# BSPD_Timing.net
KiCad netlist of a schematic drawn in Altium Designer
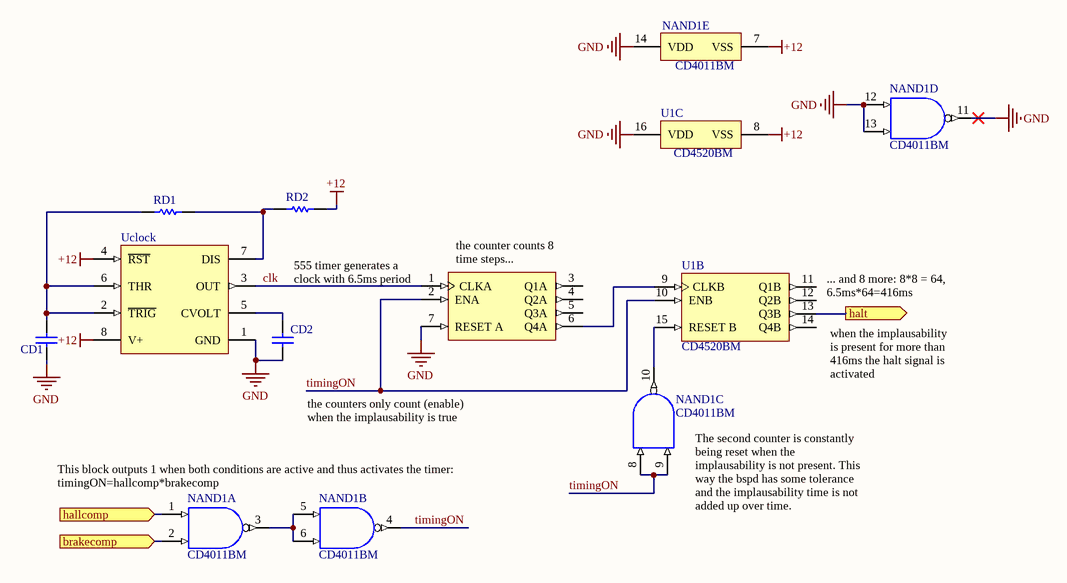
[diagram p0: BSPD_Timing.SchDoc]

(export (version "E")
  (design (tool "Eeschema 10.0.6"))
  (components
    (comp (ref "CD1")
      (value "CAP 68nF")
      (footprint "CAPC1206(3216)100_M")
      (description "CAP 68nF 50V -20% to +80% 1206 (3216 Metric) Thickness 1mm SMD")
      (fields (field (name "TOLERANCE") "-20% to +80%"))
      (libsource (lib "Altium Content Vault") (part "CAP"))
    )
    (comp (ref "CD2")
      (value "CAP 10nF")
      (footprint "CAPC1206(3216)110_M")
      (description "CAP 10nF 10V ±10% 1206 (3216 Metric) Thickness 1.05mm SMD")
      (fields (field (name "TOLERANCE") "Â±10%"))
      (libsource (lib "Altium Content Vault") (part "CAP"))
    )
    (comp (ref "NAND1")
      (value "CD4011BM")
      (footprint "D0014A_M")
      (description "CMOS Quad 2-Input NAND Gate, D0014A, TUBE")
      (fields
        (field (name "MANUFACTURER") "Texas Instruments")
        (field (name "GENERIC PART NUMBER") "CD4011B")
      )
      (libsource (lib "") (part "TI-NAND-4-2IN-14_A_1"))
    )
    (comp (ref "RD1")
      (value "68K")
      (footprint "RESC1206(3216)_M")
      (description "68K 0.25W 5% 1206 (3216 Metric)  SMD")
      (fields (field (name "TOLERANCE") "5 %") (field (name "POWER") "0.25 W"))
      (libsource (lib "Altium Content Vault") (part "RES"))
    )
    (comp (ref "RD2")
      (value "1K1")
      (footprint "RESC1206(3216)_M")
      (description "1K1 0.25W 5% 1206 (3216 Metric)  SMD")
      (fields (field (name "POWER") "0.25 W") (field (name "TOLERANCE") "5 %"))
      (libsource (lib "Altium Content Vault") (part "RES"))
    )
    (comp (ref "U1")
      (value "CD4520BM")
      (footprint "D0016A_M")
      (description "CMOS Dual Binary Up-Counter, D0016A, TUBE")
      (fields
        (field (name "GENERIC PART NUMBER") "CD4520B")
        (field (name "MANUFACTURER") "Texas Instruments")
      )
      (libsource (lib "Altium Content Vault") (part "TI-CD45XXB-16"))
    )
    (comp (ref "Uclock")
      (value "LMC555CM/NOPB")
      (footprint "D0008A_M")
      (description "CMOS Timer, 8-pin Narrow SOIC, Pb-Free")
      (fields (field (name "MANUFACTURER") "Texas Instruments"))
      (libsource (lib "Altium Content Vault") (part "AN-TIMER-LMC555-8"))
    )
  )
  (nets
    (net (code "1") (name "+12") (class "Default")
      (node (ref "NAND1") (pin "7") (pinfunction "VSS_7") (pintype "power_in"))
      (node (ref "RD2") (pin "2") (pinfunction "2_2") (pintype "passive"))
      (node (ref "U1") (pin "8") (pinfunction "VSS_8") (pintype "power_in"))
      (node (ref "Uclock") (pin "4") (pinfunction "~{RST}_4") (pintype "input"))
      (node (ref "Uclock") (pin "8") (pinfunction "V+_8") (pintype "power_in"))
    )
    (net (code "2") (name "/brakecomp") (class "Default")
      (node (ref "NAND1") (pin "2") (pinfunction "B_2") (pintype "input"))
    )
    (net (code "3") (name "/clk") (class "Default")
      (node (ref "U1") (pin "1") (pinfunction "CLKA_1") (pintype "input"))
      (node (ref "Uclock") (pin "3") (pinfunction "OUT_3") (pintype "output"))
    )
    (net (code "4") (name "/hallcomp") (class "Default")
      (node (ref "NAND1") (pin "1") (pinfunction "A_1") (pintype "input"))
    )
    (net (code "5") (name "/halt") (class "Default")
      (node (ref "U1") (pin "13") (pinfunction "Q3B_13") (pintype "output"))
    )
    (net (code "6") (name "/timingON") (class "Default")
      (node (ref "NAND1") (pin "4") (pinfunction "K_4") (pintype "output"))
      (node (ref "NAND1") (pin "8") (pinfunction "E_8") (pintype "input"))
      (node (ref "NAND1") (pin "9") (pinfunction "F_9") (pintype "input"))
      (node (ref "U1") (pin "10") (pinfunction "ENB_10") (pintype "input"))
      (node (ref "U1") (pin "2") (pinfunction "ENA_2") (pintype "input"))
    )
    (net (code "7") (name "GND") (class "Default")
      (node (ref "CD1") (pin "2") (pinfunction "2_2") (pintype "passive"))
      (node (ref "CD2") (pin "2") (pinfunction "2_2") (pintype "passive"))
      (node (ref "NAND1") (pin "11") (pinfunction "M_11") (pintype "output"))
      (node (ref "NAND1") (pin "12") (pinfunction "G_12") (pintype "input"))
      (node (ref "NAND1") (pin "13") (pinfunction "H_13") (pintype "input"))
      (node (ref "NAND1") (pin "14") (pinfunction "VDD_14") (pintype "power_in"))
      (node (ref "U1") (pin "16") (pinfunction "VDD_16") (pintype "power_in"))
      (node (ref "U1") (pin "7") (pinfunction "RESET_A_7") (pintype "input"))
      (node (ref "Uclock") (pin "1") (pinfunction "GND_1") (pintype "power_in"))
    )
    (net (code "8") (name "Net-(NAND1A-J)") (class "Default")
      (node (ref "NAND1") (pin "3") (pinfunction "J_3") (pintype "output"))
      (node (ref "NAND1") (pin "5") (pinfunction "C_5") (pintype "input"))
      (node (ref "NAND1") (pin "6") (pinfunction "D_6") (pintype "input"))
    )
    (net (code "9") (name "Net-(NAND1C-L)") (class "Default")
      (node (ref "NAND1") (pin "10") (pinfunction "L_10") (pintype "output"))
      (node (ref "U1") (pin "15") (pinfunction "RESET_B_15") (pintype "input"))
    )
    (net (code "10") (name "Net-(U1A-Q4A)") (class "Default")
      (node (ref "U1") (pin "6") (pinfunction "Q4A_6") (pintype "output"))
      (node (ref "U1") (pin "9") (pinfunction "CLKB_9") (pintype "input"))
    )
    (net (code "11") (name "Net-(Uclock-CVOLT)") (class "Default")
      (node (ref "CD2") (pin "1") (pinfunction "1_1") (pintype "passive"))
      (node (ref "Uclock") (pin "5") (pinfunction "CVOLT_5") (pintype "passive"))
    )
    (net (code "12") (name "Net-(Uclock-DIS)") (class "Default")
      (node (ref "RD1") (pin "2") (pinfunction "2_2") (pintype "passive"))
      (node (ref "RD2") (pin "1") (pinfunction "1_1") (pintype "passive"))
      (node (ref "Uclock") (pin "7") (pinfunction "DIS_7") (pintype "open_collector"))
    )
    (net (code "13") (name "Net-(Uclock-THR)") (class "Default")
      (node (ref "CD1") (pin "1") (pinfunction "1_1") (pintype "passive"))
      (node (ref "RD1") (pin "1") (pinfunction "1_1") (pintype "passive"))
      (node (ref "Uclock") (pin "2") (pinfunction "~{TRIG}_2") (pintype "input"))
      (node (ref "Uclock") (pin "6") (pinfunction "THR_6") (pintype "input"))
    )
    (net (code "14") (name "unconnected-(U1A-Q1A-Pad3)") (class "Default")
      (node (ref "U1") (pin "3") (pinfunction "Q1A_3") (pintype "output"))
    )
    (net (code "15") (name "unconnected-(U1A-Q2A-Pad4)") (class "Default")
      (node (ref "U1") (pin "4") (pinfunction "Q2A_4") (pintype "output"))
    )
    (net (code "16") (name "unconnected-(U1A-Q3A-Pad5)") (class "Default")
      (node (ref "U1") (pin "5") (pinfunction "Q3A_5") (pintype "output"))
    )
    (net (code "17") (name "unconnected-(U1B-Q1B-Pad11)") (class "Default")
      (node (ref "U1") (pin "11") (pinfunction "Q1B_11") (pintype "output"))
    )
    (net (code "18") (name "unconnected-(U1B-Q2B-Pad12)") (class "Default")
      (node (ref "U1") (pin "12") (pinfunction "Q2B_12") (pintype "output"))
    )
    (net (code "19") (name "unconnected-(U1B-Q4B-Pad14)") (class "Default")
      (node (ref "U1") (pin "14") (pinfunction "Q4B_14") (pintype "output"))
    )
  )
)
